# Sheet1.net
KiCad netlist of a schematic drawn in Altium Designer
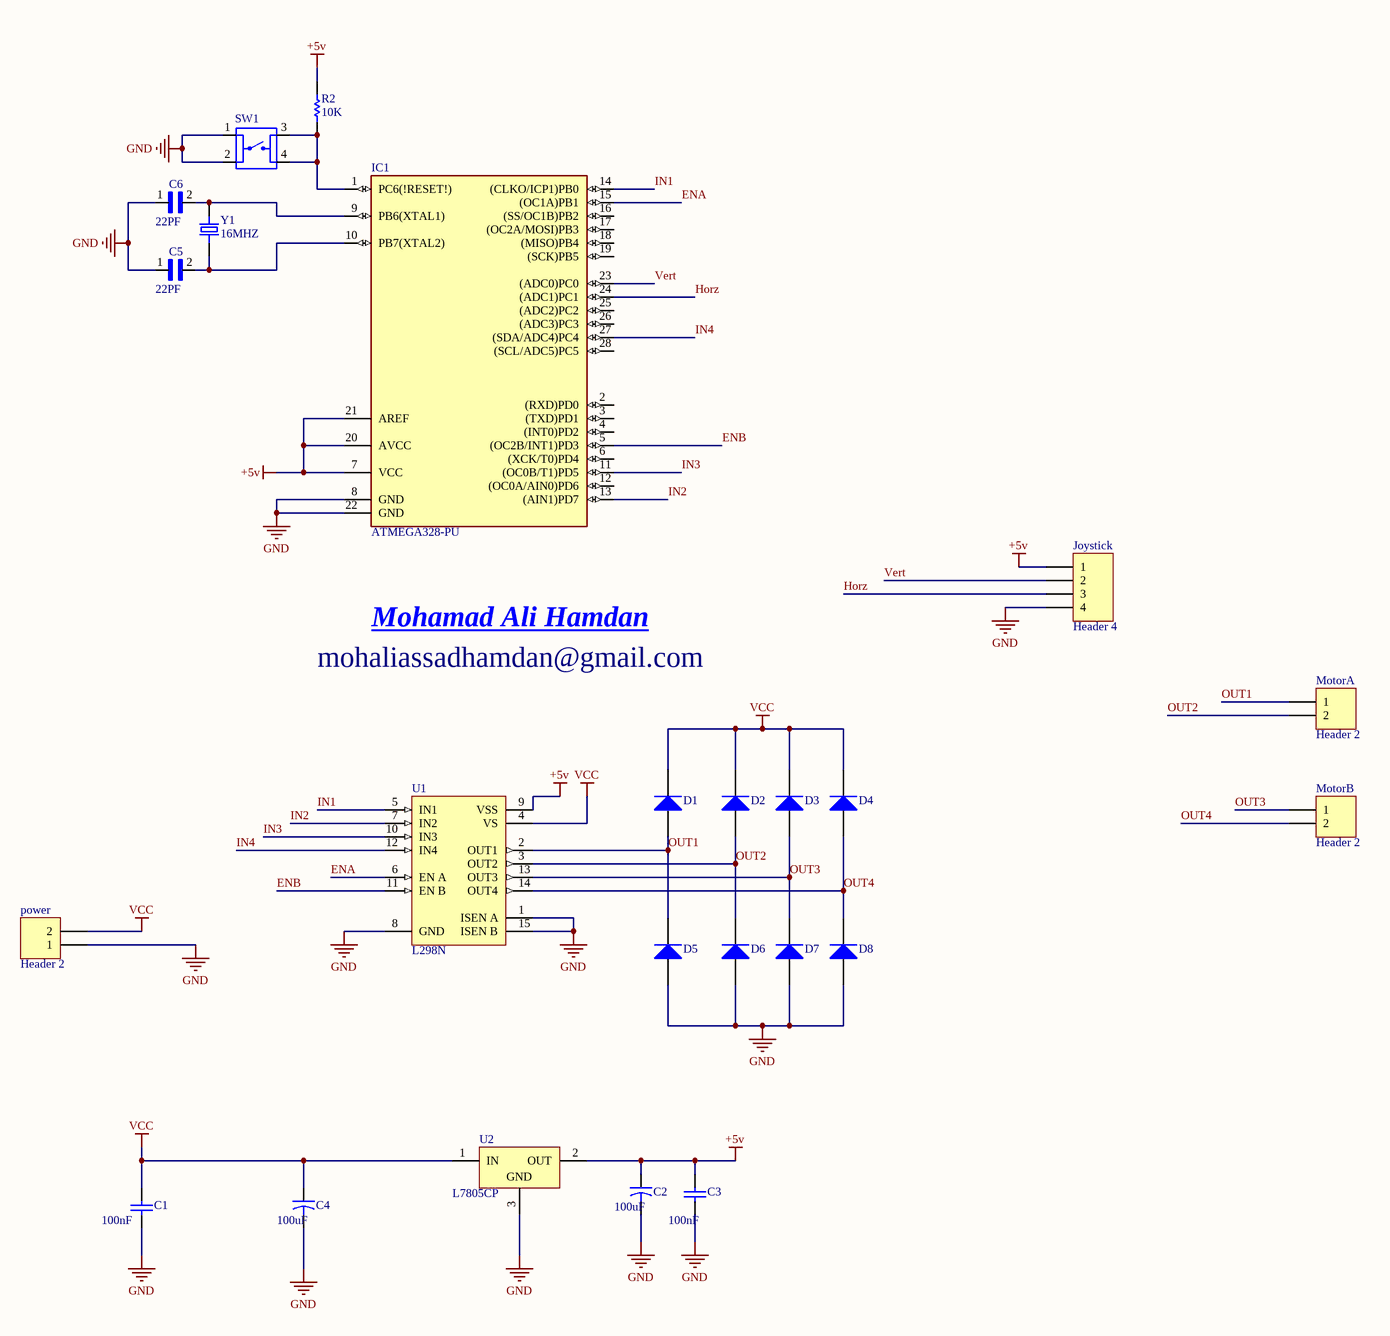
[diagram p0: Sheet1.SchDoc]

(export (version "E")
  (design (tool "Eeschema 10.0.6"))
  (components
    (comp (ref "C1")
      (value "100nF")
      (footprint "CAP_RDER71H333K0M1H03A")
      (description "Capacitor")
      (fields (field (name "Comment") "Cap") (field (name "PUBLISHER") "Altium Limited"))
      (libsource (lib "Miscellaneous Devices") (part "Cap"))
    )
    (comp (ref "C2")
      (value "100uF")
      (footprint "Capacitor_pol")
      (description "Capacitor")
      (fields (field (name "Comment") "Cap2") (field (name "PUBLISHER") "Altium Limited"))
      (libsource (lib "Miscellaneous Devices") (part "Cap2"))
    )
    (comp (ref "C3")
      (value "100nF")
      (footprint "CAP_RDER71H333K0M1H03A")
      (description "Capacitor")
      (fields (field (name "Comment") "Cap") (field (name "PUBLISHER") "Altium Limited"))
      (libsource (lib "Miscellaneous Devices") (part "Cap"))
    )
    (comp (ref "C4")
      (value "100uF")
      (footprint "Capacitor_pol")
      (description "Capacitor")
      (fields (field (name "Comment") "Cap2") (field (name "PUBLISHER") "Altium Limited"))
      (libsource (lib "Miscellaneous Devices") (part "Cap2"))
    )
    (comp (ref "C5")
      (value "14pF")
      (footprint "CAP_RDER71H333K0M1H03A")
      (description "Lead capacitor X7R(EIA) with Capacitance 33000pF, Rated Voltage 50Vdc")
      (fields
        (field (name "MF") "Murata")
        (field (name "MP") "RDER71H333K0M1H03A")
        (field (name "BUYPART") "22PF")
      )
      (libsource (lib "RDER71H333K0M1H03A") (part "RDER71H333K0M1H03A"))
    )
    (comp (ref "C6")
      (value "14pF")
      (footprint "CAP_RDER71H333K0M1H03A")
      (description "Lead capacitor X7R(EIA) with Capacitance 33000pF, Rated Voltage 50Vdc")
      (fields
        (field (name "MF") "Murata")
        (field (name "MP") "RDER71H333K0M1H03A")
        (field (name "BUYPART") "22PF")
      )
      (libsource (lib "RDER71H333K0M1H03A") (part "RDER71H333K0M1H03A"))
    )
    (comp (ref "D1")
      (value "Diode 1N914")
      (footprint "diode 4007")
      (description "High Conductance Fast Diode")
      (fields (field (name "PUBLISHER") "Altium Limited"))
      (libsource (lib "Miscellaneous Devices") (part "Diode 1N914"))
    )
    (comp (ref "D2")
      (value "Diode 1N914")
      (footprint "diode 4007")
      (description "High Conductance Fast Diode")
      (fields (field (name "PUBLISHER") "Altium Limited"))
      (libsource (lib "Miscellaneous Devices") (part "Diode 1N914"))
    )
    (comp (ref "D3")
      (value "Diode 1N914")
      (footprint "diode 4007")
      (description "High Conductance Fast Diode")
      (fields (field (name "PUBLISHER") "Altium Limited"))
      (libsource (lib "Miscellaneous Devices") (part "Diode 1N914"))
    )
    (comp (ref "D4")
      (value "Diode 1N914")
      (footprint "diode 4007")
      (description "High Conductance Fast Diode")
      (fields (field (name "PUBLISHER") "Altium Limited"))
      (libsource (lib "Miscellaneous Devices") (part "Diode 1N914"))
    )
    (comp (ref "D5")
      (value "Diode 1N914")
      (footprint "diode 4007")
      (description "High Conductance Fast Diode")
      (fields (field (name "PUBLISHER") "Altium Limited"))
      (libsource (lib "Miscellaneous Devices") (part "Diode 1N914"))
    )
    (comp (ref "D6")
      (value "Diode 1N914")
      (footprint "diode 4007")
      (description "High Conductance Fast Diode")
      (fields (field (name "PUBLISHER") "Altium Limited"))
      (libsource (lib "Miscellaneous Devices") (part "Diode 1N914"))
    )
    (comp (ref "D7")
      (value "Diode 1N914")
      (footprint "diode 4007")
      (description "High Conductance Fast Diode")
      (fields (field (name "PUBLISHER") "Altium Limited"))
      (libsource (lib "Miscellaneous Devices") (part "Diode 1N914"))
    )
    (comp (ref "D8")
      (value "Diode 1N914")
      (footprint "diode 4007")
      (description "High Conductance Fast Diode")
      (fields (field (name "PUBLISHER") "Altium Limited"))
      (libsource (lib "Miscellaneous Devices") (part "Diode 1N914"))
    )
    (comp (ref "IC1")
      (value "ATMEGA328-PU")
      (footprint "Atmega:DIL28")
      (description "AVR AVRÂ® ATmega Microcontroller IC 8-Bit 20MHz 32KB _16K x 16_ FLASH 28-PDIP")
      (fields (field (name "MF") "Microchip Technology"))
      (libsource (lib "Atmega328PU") (part "ATMEGA328-PU"))
    )
    (comp (ref "Joystick")
      (value "Header 4")
      (footprint "TE_2355172-4")
      (description "Header, 4-Pin")
      (fields (field (name "PUBLISHER") "Altium Limited"))
      (libsource (lib "Miscellaneous Connectors") (part "Header 4"))
    )
    (comp (ref "MotorA")
      (value "Header 2")
      (footprint "blue_connector_2pins")
      (description "Header, 2-Pin")
      (fields (field (name "PUBLISHER") "Altium Limited"))
      (libsource (lib "Miscellaneous Connectors") (part "Header 2"))
    )
    (comp (ref "MotorB")
      (value "Header 2")
      (footprint "blue_connector_2pins")
      (description "Header, 2-Pin")
      (fields (field (name "PUBLISHER") "Altium Limited"))
      (libsource (lib "Miscellaneous Connectors") (part "Header 2"))
    )
    (comp (ref "power")
      (value "Header 2")
      (footprint "blue_connector_2pins")
      (description "Header, 2-Pin")
      (fields (field (name "PUBLISHER") "Altium Limited"))
      (libsource (lib "") (part "Header 2_1"))
    )
    (comp (ref "R2")
      (value "10K")
      (footprint "resistor")
      (description "Resistor")
      (fields (field (name "Comment") "Res1") (field (name "PUBLISHER") "Altium Limited"))
      (libsource (lib "Miscellaneous Devices") (part "Res1"))
    )
    (comp (ref "SW1")
      (value "FSM8JH")
      (footprint "SW_FSM8JH")
      (description "Tactile Switch SPST-NO Top Actuated Through Hole")
      (fields (field (name "MF") "TE Connectivity"))
      (libsource (lib "switch") (part "FSM8JH"))
    )
    (comp (ref "U1")
      (value "L298N")
      (footprint "TO127P2020X500X2100-15")
      (description "Dual Full Bridge Driver")
      (fields (field (name "PUBLISHER") "Altium Limited"))
      (libsource (lib "ST Interface DC Motor Controller") (part "L298N"))
    )
    (comp (ref "U2")
      (value "L7805CP")
      (footprint "LM7805")
      (description "Positive Voltage Regulator")
      (fields (field (name "PUBLISHER") "Altium Limited"))
      (libsource (lib "ST Power Mgt Voltage Regulator") (part "L7805CP"))
    )
    (comp (ref "Y1")
      (value "16MHZ")
      (footprint "XTAL_ECS-160-20-4VX")
      (description "16MHz Â±30ppm Crystal 20pF 50 Ohms HC-49/US")
      (fields (field (name "MF") "ECS Inc.") (field (name "MP") "ECS-160-20-4VX"))
      (libsource (lib "Crystal") (part "ECS-160-20-4VX"))
    )
  )
  (nets
    (net (code "1") (name "+5v") (class "Default")
      (node (ref "C2") (pin "1") (pinfunction "1_1") (pintype "passive"))
      (node (ref "C3") (pin "2") (pinfunction "2_2") (pintype "passive"))
      (node (ref "IC1") (pin "20") (pinfunction "AVCC_20") (pintype "power_in"))
      (node (ref "IC1") (pin "21") (pinfunction "AREF_21") (pintype "passive"))
      (node (ref "IC1") (pin "7") (pinfunction "VCC_7") (pintype "power_in"))
      (node (ref "Joystick") (pin "1") (pinfunction "1_1") (pintype "passive"))
      (node (ref "R2") (pin "2") (pinfunction "2_2") (pintype "passive"))
      (node (ref "U1") (pin "9") (pinfunction "VSS_9") (pintype "power_in"))
      (node (ref "U2") (pin "2") (pinfunction "OUT_2") (pintype "power_in"))
    )
    (net (code "2") (name "/ENA") (class "Default")
      (node (ref "IC1") (pin "15") (pinfunction "(OC1A)PB1_15") (pintype "bidirectional"))
      (node (ref "U1") (pin "6") (pinfunction "EN_A_6") (pintype "input"))
    )
    (net (code "3") (name "/ENB") (class "Default")
      (node (ref "IC1") (pin "5") (pinfunction "(OC2B/INT1)PD3_5") (pintype "bidirectional"))
      (node (ref "U1") (pin "11") (pinfunction "EN_B_11") (pintype "input"))
    )
    (net (code "4") (name "/Horz") (class "Default")
      (node (ref "IC1") (pin "24") (pinfunction "(ADC1)PC1_24") (pintype "bidirectional"))
      (node (ref "Joystick") (pin "3") (pinfunction "3_3") (pintype "passive"))
    )
    (net (code "5") (name "/IN1") (class "Default")
      (node (ref "IC1") (pin "14") (pinfunction "(CLKO/ICP1)PB0_14") (pintype "bidirectional"))
      (node (ref "U1") (pin "5") (pinfunction "IN1_5") (pintype "input"))
    )
    (net (code "6") (name "/IN2") (class "Default")
      (node (ref "IC1") (pin "13") (pinfunction "(AIN1)PD7_13") (pintype "bidirectional"))
      (node (ref "U1") (pin "7") (pinfunction "IN2_7") (pintype "input"))
    )
    (net (code "7") (name "/IN3") (class "Default")
      (node (ref "IC1") (pin "11") (pinfunction "(OC0B/T1)PD5_11") (pintype "bidirectional"))
      (node (ref "U1") (pin "10") (pinfunction "IN3_10") (pintype "input"))
    )
    (net (code "8") (name "/IN4") (class "Default")
      (node (ref "IC1") (pin "27") (pinfunction "(SDA/ADC4)PC4_27") (pintype "bidirectional"))
      (node (ref "U1") (pin "12") (pinfunction "IN4_12") (pintype "input"))
    )
    (net (code "9") (name "/OUT1") (class "Default")
      (node (ref "D1") (pin "1") (pinfunction "A_1") (pintype "passive"))
      (node (ref "D5") (pin "2") (pinfunction "K_2") (pintype "passive"))
      (node (ref "MotorA") (pin "1") (pinfunction "1_1") (pintype "passive"))
      (node (ref "U1") (pin "2") (pinfunction "OUT1_2") (pintype "output"))
    )
    (net (code "10") (name "/OUT2") (class "Default")
      (node (ref "D2") (pin "1") (pinfunction "A_1") (pintype "passive"))
      (node (ref "D6") (pin "2") (pinfunction "K_2") (pintype "passive"))
      (node (ref "MotorA") (pin "2") (pinfunction "2_2") (pintype "passive"))
      (node (ref "U1") (pin "3") (pinfunction "OUT2_3") (pintype "output"))
    )
    (net (code "11") (name "/OUT3") (class "Default")
      (node (ref "D3") (pin "1") (pinfunction "A_1") (pintype "passive"))
      (node (ref "D7") (pin "2") (pinfunction "K_2") (pintype "passive"))
      (node (ref "MotorB") (pin "1") (pinfunction "1_1") (pintype "passive"))
      (node (ref "U1") (pin "13") (pinfunction "OUT3_13") (pintype "output"))
    )
    (net (code "12") (name "/OUT4") (class "Default")
      (node (ref "D4") (pin "1") (pinfunction "A_1") (pintype "passive"))
      (node (ref "D8") (pin "2") (pinfunction "K_2") (pintype "passive"))
      (node (ref "MotorB") (pin "2") (pinfunction "2_2") (pintype "passive"))
      (node (ref "U1") (pin "14") (pinfunction "OUT4_14") (pintype "output"))
    )
    (net (code "13") (name "/Vert") (class "Default")
      (node (ref "IC1") (pin "23") (pinfunction "(ADC0)PC0_23") (pintype "bidirectional"))
      (node (ref "Joystick") (pin "2") (pinfunction "2_2") (pintype "passive"))
    )
    (net (code "14") (name "GND") (class "Default")
      (node (ref "C1") (pin "1") (pinfunction "1_1") (pintype "passive"))
      (node (ref "C2") (pin "2") (pinfunction "2_2") (pintype "passive"))
      (node (ref "C3") (pin "1") (pinfunction "1_1") (pintype "passive"))
      (node (ref "C4") (pin "2") (pinfunction "2_2") (pintype "passive"))
      (node (ref "C5") (pin "1") (pinfunction "1_1") (pintype "passive"))
      (node (ref "C6") (pin "1") (pinfunction "1_1") (pintype "passive"))
      (node (ref "D5") (pin "1") (pinfunction "A_1") (pintype "passive"))
      (node (ref "D6") (pin "1") (pinfunction "A_1") (pintype "passive"))
      (node (ref "D7") (pin "1") (pinfunction "A_1") (pintype "passive"))
      (node (ref "D8") (pin "1") (pinfunction "A_1") (pintype "passive"))
      (node (ref "IC1") (pin "22") (pinfunction "GND_22") (pintype "power_in"))
      (node (ref "IC1") (pin "8") (pinfunction "GND_8") (pintype "power_in"))
      (node (ref "Joystick") (pin "4") (pinfunction "4_4") (pintype "passive"))
      (node (ref "SW1") (pin "1") (pinfunction "1_1") (pintype "passive"))
      (node (ref "SW1") (pin "2") (pinfunction "2_2") (pintype "passive"))
      (node (ref "U1") (pin "1") (pinfunction "ISEN_A_1") (pintype "passive"))
      (node (ref "U1") (pin "15") (pinfunction "ISEN_B_15") (pintype "passive"))
      (node (ref "U1") (pin "8") (pinfunction "GND_8") (pintype "power_in"))
      (node (ref "U2") (pin "3") (pinfunction "GND_3") (pintype "power_in"))
      (node (ref "power") (pin "1") (pinfunction "1_1") (pintype "passive"))
    )
    (net (code "15") (name "Net-(IC1-PB6(XTAL1))") (class "Default")
      (node (ref "C6") (pin "2") (pinfunction "2_2") (pintype "passive"))
      (node (ref "IC1") (pin "9") (pinfunction "PB6(XTAL1)_9") (pintype "bidirectional"))
      (node (ref "Y1") (pin "2") (pinfunction "2_2") (pintype "passive"))
    )
    (net (code "16") (name "Net-(IC1-PB7(XTAL2))") (class "Default")
      (node (ref "C5") (pin "2") (pinfunction "2_2") (pintype "passive"))
      (node (ref "IC1") (pin "10") (pinfunction "PB7(XTAL2)_10") (pintype "bidirectional"))
      (node (ref "Y1") (pin "1") (pinfunction "1_1") (pintype "passive"))
    )
    (net (code "17") (name "Net-(IC1-PC6(!RESET!))") (class "Default")
      (node (ref "IC1") (pin "1") (pinfunction "PC6(!RESET!)_1") (pintype "bidirectional"))
      (node (ref "R2") (pin "1") (pinfunction "1_1") (pintype "passive"))
      (node (ref "SW1") (pin "3") (pinfunction "3_3") (pintype "passive"))
      (node (ref "SW1") (pin "4") (pinfunction "4_4") (pintype "passive"))
    )
    (net (code "18") (name "VCC") (class "Default")
      (node (ref "C1") (pin "2") (pinfunction "2_2") (pintype "passive"))
      (node (ref "C4") (pin "1") (pinfunction "1_1") (pintype "passive"))
      (node (ref "D1") (pin "2") (pinfunction "K_2") (pintype "passive"))
      (node (ref "D2") (pin "2") (pinfunction "K_2") (pintype "passive"))
      (node (ref "D3") (pin "2") (pinfunction "K_2") (pintype "passive"))
      (node (ref "D4") (pin "2") (pinfunction "K_2") (pintype "passive"))
      (node (ref "U1") (pin "4") (pinfunction "VS_4") (pintype "power_in"))
      (node (ref "U2") (pin "1") (pinfunction "IN_1") (pintype "power_in"))
      (node (ref "power") (pin "2") (pinfunction "2_2") (pintype "passive"))
    )
    (net (code "19") (name "unconnected-(IC1-(ADC2)PC2-Pad25)") (class "Default")
      (node (ref "IC1") (pin "25") (pinfunction "(ADC2)PC2_25") (pintype "bidirectional"))
    )
    (net (code "20") (name "unconnected-(IC1-(ADC3)PC3-Pad26)") (class "Default")
      (node (ref "IC1") (pin "26") (pinfunction "(ADC3)PC3_26") (pintype "bidirectional"))
    )
    (net (code "21") (name "unconnected-(IC1-(INT0)PD2-Pad4)") (class "Default")
      (node (ref "IC1") (pin "4") (pinfunction "(INT0)PD2_4") (pintype "bidirectional"))
    )
    (net (code "22") (name "unconnected-(IC1-(MISO)PB4-Pad18)") (class "Default")
      (node (ref "IC1") (pin "18") (pinfunction "(MISO)PB4_18") (pintype "bidirectional"))
    )
    (net (code "23") (name "unconnected-(IC1-(OC0A{slash}AIN0)PD6-Pad12)") (class "Default")
      (node (ref "IC1") (pin "12") (pinfunction "(OC0A/AIN0)PD6_12") (pintype "bidirectional"))
    )
    (net (code "24") (name "unconnected-(IC1-(OC2A{slash}MOSI)PB3-Pad17)") (class "Default")
      (node (ref "IC1") (pin "17") (pinfunction "(OC2A/MOSI)PB3_17") (pintype "bidirectional"))
    )
    (net (code "25") (name "unconnected-(IC1-(RXD)PD0-Pad2)") (class "Default")
      (node (ref "IC1") (pin "2") (pinfunction "(RXD)PD0_2") (pintype "bidirectional"))
    )
    (net (code "26") (name "unconnected-(IC1-(SCK)PB5-Pad19)") (class "Default")
      (node (ref "IC1") (pin "19") (pinfunction "(SCK)PB5_19") (pintype "bidirectional"))
    )
    (net (code "27") (name "unconnected-(IC1-(SCL{slash}ADC5)PC5-Pad28)") (class "Default")
      (node (ref "IC1") (pin "28") (pinfunction "(SCL/ADC5)PC5_28") (pintype "bidirectional"))
    )
    (net (code "28") (name "unconnected-(IC1-(SS{slash}OC1B)PB2-Pad16)") (class "Default")
      (node (ref "IC1") (pin "16") (pinfunction "(SS/OC1B)PB2_16") (pintype "bidirectional"))
    )
    (net (code "29") (name "unconnected-(IC1-(TXD)PD1-Pad3)") (class "Default")
      (node (ref "IC1") (pin "3") (pinfunction "(TXD)PD1_3") (pintype "bidirectional"))
    )
    (net (code "30") (name "unconnected-(IC1-(XCK{slash}T0)PD4-Pad6)") (class "Default")
      (node (ref "IC1") (pin "6") (pinfunction "(XCK/T0)PD4_6") (pintype "bidirectional"))
    )
  )
)
